# Digital_MEMS_Microphone_Backend.net
KiCad netlist of a schematic drawn in Altium Designer
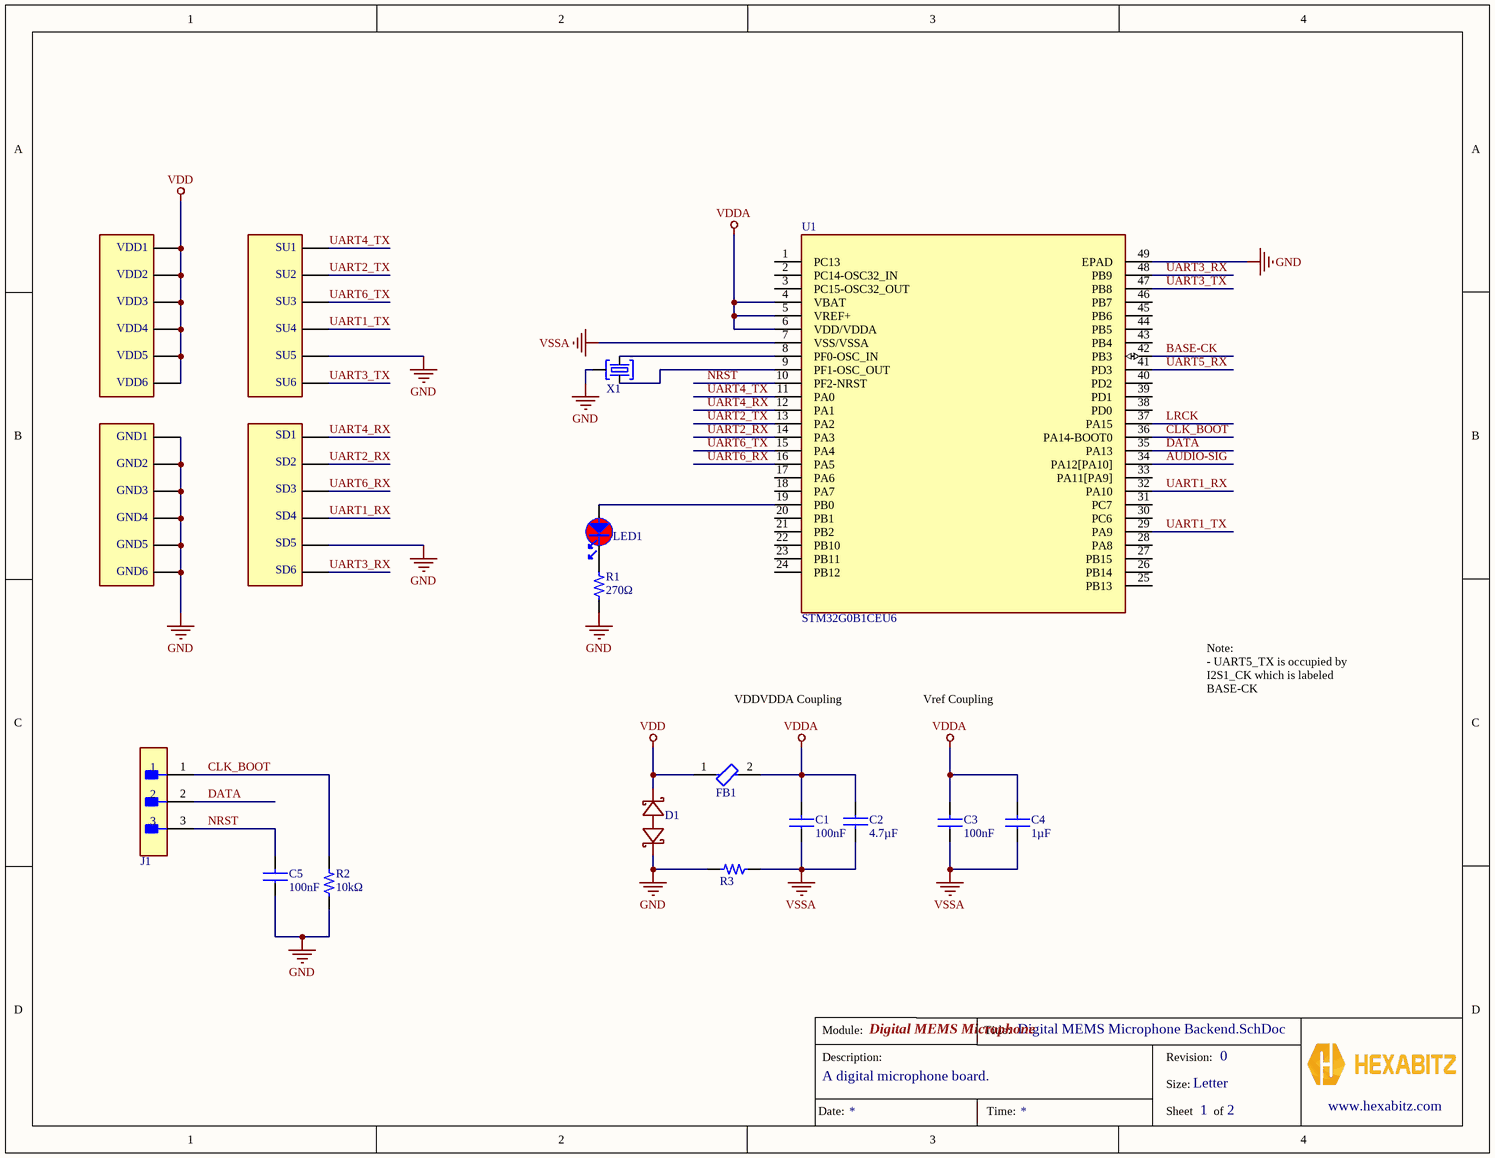
[diagram p0: Digital MEMS Microphone Backend.SchDoc]

(export (version "E")
  (design (tool "Eeschema 10.0.6"))
  (components
    (comp (ref "C1")
      (value "100nF")
      (footprint "C0603")
      (fields
        (field (name "MANUFACTURER") "Samsung Electro-Mechanics")
        (field (name "MANUFACTURER PART NUMBER") "CL10B104KA8NNNC")
        (field (name "TOLERANCE") "10%")
      )
      (libsource (lib "Hexabitz Altium Library") (part "generic Capacitor"))
    )
    (comp (ref "C2")
      (value "4.7µF")
      (footprint "C0805")
      (fields
        (field (name "MANUFACTURER") "Samsung Electro-Mechanics")
        (field (name "MANUFACTURER PART NUMBER") "CL21X475KAQNNNE")
        (field (name "TOLERANCE") "10%")
      )
      (libsource (lib "Hexabitz Altium Library") (part "generic Capacitor"))
    )
    (comp (ref "C3")
      (value "100nF")
      (footprint "C0603")
      (fields
        (field (name "MANUFACTURER") "Samsung Electro-Mechanics")
        (field (name "MANUFACTURER PART NUMBER") "CL10B104KA8NNNC")
        (field (name "TOLERANCE") "10%")
      )
      (libsource (lib "Hexabitz Altium Library") (part "generic Capacitor"))
    )
    (comp (ref "C4")
      (value "1µF")
      (footprint "C0805")
      (description "Ceramic Capacitor, Ceramic, 16V, 10% +Tol, 10% -Tol, X7R, 15% TC, 1uF, Surface Mount, 0805")
      (fields
        (field (name "MANUFACTURER") "Yageo Group")
        (field (name "MANUFACTURER PART NUMBER") "CC0805KKX7R7BB105")
      )
      (libsource (lib "Hexabitz Altium Library") (part "generic Capacitor"))
    )
    (comp (ref "C5")
      (value "100nF")
      (footprint "C0603")
      (fields
        (field (name "MANUFACTURER") "Samsung Electro-Mechanics")
        (field (name "MANUFACTURER PART NUMBER") "CL10B104KA8NNNC")
        (field (name "TOLERANCE") "10%")
      )
      (libsource (lib "Hexabitz Altium Library") (part "generic Capacitor"))
    )
    (comp (ref "D1")
      (value "CDSOD323-T03SC")
      (footprint "SOD2513X114N")
      (description "A 3V, 350W, bi-directional, standard capacitance, SOD323 pkg TVS Diode ¦ Bourns CDSOD323-T03SC")
      (fields (field (name "MANUFACTURER") "Bourns"))
      (libsource (lib "Hexabitz Altium Library") (part "CDSOD323-T03SC"))
    )
    (comp (ref "FB1")
      (value "MMZ1608Y300B")
      (footprint "FP-MMZ1608-0_8-MFG")
      (description "Ferrite Beads 0603 30ohms 1500mA Signal Line AEC-Q200")
      (fields
        (field (name "MANUFACTURER") "TDK")
        (field (name "MANUFACTURER PART NUMBER") "MMZ1608Y300BTD25")
      )
      (libsource (lib "Hexabitz Altium Library") (part "MMZ1608Y300B"))
    )
    (comp (ref "GND1")
      (value "HEXABIT_UART_PORT")
      (footprint "HEXABIT_POWER_PORT_D")
      (libsource (lib "hexabitz_connectors.Library") (part "HEXABIT_POWER_PORT_D"))
    )
    (comp (ref "GND2")
      (value "HEXABIT_UART_PORT")
      (footprint "HEXABIT_POWER_PORT_D")
      (libsource (lib "hexabitz_connectors.Library") (part "HEXABIT_POWER_PORT_D"))
    )
    (comp (ref "GND3")
      (value "HEXABIT_UART_PORT")
      (footprint "HEXABIT_POWER_PORT_D")
      (libsource (lib "hexabitz_connectors.Library") (part "HEXABIT_POWER_PORT_D"))
    )
    (comp (ref "GND4")
      (value "HEXABIT_UART_PORT")
      (footprint "HEXABIT_POWER_PORT_D")
      (libsource (lib "hexabitz_connectors.Library") (part "HEXABIT_POWER_PORT_D"))
    )
    (comp (ref "GND5")
      (value "HEXABIT_UART_PORT")
      (footprint "HEXABIT_POWER_PORT_D")
      (libsource (lib "hexabitz_connectors.Library") (part "HEXABIT_POWER_PORT_D"))
    )
    (comp (ref "GND6")
      (value "HEXABIT_UART_PORT")
      (footprint "HEXABIT_POWER_PORT_D")
      (libsource (lib "hexabitz_connectors.Library") (part "HEXABIT_POWER_PORT_D"))
    )
    (comp (ref "J1")
      (value "TSW-103-14-G-S")
      (footprint "FP-TSW-103-14-G-S-MFG")
      (description "CONN HEADER VERT 3POS 2.54MM")
      (libsource (lib "Altium Content Vault") (part "cd3439d6ef35ae5d9b27ec4fdd3e828"))
    )
    (comp (ref "LED1")
      (value "VLMS1300-GS08")
      (footprint "FP-6_541-5092_01-4-MFG")
      (description "LED Uni-Color Super Red 639nm 2-Pin Chip 0603(1608Metric) T/R")
      (fields (field (name "MANUFACTURER") "Vishay Semiconductors"))
      (libsource (lib "Hexabitz Altium Library") (part "VLMS1300-GS08"))
    )
    (comp (ref "R1")
      (value "270Ω")
      (footprint "R0603")
      (description "Res Thick Film 0603 270 Ohm 5% 0.1W(1/10W) ±200ppm/C Pad SMD Automotive T/R")
      (fields
        (field (name "MANUFACTURER") "Panasonic")
        (field (name "MANUFACTURER PART NUMBER") "ERJ-3GEYJ271V")
      )
      (libsource (lib "") (part "generic Resistor_1"))
    )
    (comp (ref "R2")
      (value "10kΩ")
      (footprint "R0603")
      (description "100mW Thick Film Resistors ±100ppm/℃ ±1% 10kΩ 0603 Chip Resistor - Surface Mount ROHS")
      (fields
        (field (name "MANUFACTURER") "Yageo Group")
        (field (name "MANUFACTURER PART NUMBER") "RC0603FR-0710KL")
      )
      (libsource (lib "Hexabitz Altium Library") (part "generic Resistor"))
    )
    (comp (ref "R3")
      (value "Manufacturer Part Number")
      (footprint "R0603")
      (libsource (lib "") (part "generic Resistor_2"))
    )
    (comp (ref "SD1")
      (value "HEXABIT_UART_PORT")
      (footprint "HEXABIT_UART_PORT_D")
      (libsource (lib "hexabitz_connectors.Library") (part "HEXABIT_UART_PORT_D"))
    )
    (comp (ref "SD2")
      (value "HEXABIT_UART_PORT")
      (footprint "HEXABIT_UART_PORT_D")
      (libsource (lib "hexabitz_connectors.Library") (part "HEXABIT_UART_PORT_D"))
    )
    (comp (ref "SD3")
      (value "HEXABIT_UART_PORT")
      (footprint "HEXABIT_UART_PORT_D")
      (libsource (lib "hexabitz_connectors.Library") (part "HEXABIT_UART_PORT_D"))
    )
    (comp (ref "SD4")
      (value "HEXABIT_UART_PORT")
      (footprint "HEXABIT_UART_PORT_D")
      (libsource (lib "hexabitz_connectors.Library") (part "HEXABIT_UART_PORT_D"))
    )
    (comp (ref "SD5")
      (value "HEXABIT_UART_PORT")
      (footprint "HEXABIT_UART_PORT_D")
      (libsource (lib "hexabitz_connectors.Library") (part "HEXABIT_UART_PORT_D"))
    )
    (comp (ref "SD6")
      (value "HEXABIT_UART_PORT")
      (footprint "HEXABIT_UART_PORT_D")
      (libsource (lib "hexabitz_connectors.Library") (part "HEXABIT_UART_PORT_D"))
    )
    (comp (ref "SU1")
      (value "HEXABIT_UART_PORT")
      (footprint "HEXABIT_UART_PORT_U")
      (libsource (lib "hexabitz_connectors.Library") (part "HEXABIT_UART_PORT_U"))
    )
    (comp (ref "SU2")
      (value "HEXABIT_UART_PORT")
      (footprint "HEXABIT_UART_PORT_U")
      (libsource (lib "hexabitz_connectors.Library") (part "HEXABIT_UART_PORT_U"))
    )
    (comp (ref "SU3")
      (value "HEXABIT_UART_PORT")
      (footprint "HEXABIT_UART_PORT_U")
      (libsource (lib "hexabitz_connectors.Library") (part "HEXABIT_UART_PORT_U"))
    )
    (comp (ref "SU4")
      (value "HEXABIT_UART_PORT")
      (footprint "HEXABIT_UART_PORT_U")
      (libsource (lib "hexabitz_connectors.Library") (part "HEXABIT_UART_PORT_U"))
    )
    (comp (ref "SU5")
      (value "HEXABIT_UART_PORT")
      (footprint "HEXABIT_UART_PORT_U")
      (libsource (lib "hexabitz_connectors.Library") (part "HEXABIT_UART_PORT_U"))
    )
    (comp (ref "SU6")
      (value "HEXABIT_UART_PORT")
      (footprint "HEXABIT_UART_PORT_U")
      (libsource (lib "hexabitz_connectors.Library") (part "HEXABIT_UART_PORT_U"))
    )
    (comp (ref "U1")
      (value "STM32G0B1CEU6")
      (footprint "QFN50P700X700X65-49N-D")
      (description "MCU 32-bit ARM Cortex M0+ RISC 512KB Flash 1.8V/2.5V/3.3V 48-Pin UFQFPN EP Tray")
      (fields
        (field (name "MANUFACTURER") "STMicroelectronics")
        (field (name "MANUFACTURER PART NUMBER") "STM32G0B1CEU6")
      )
      (libsource (lib "Hexabitz Altium Library") (part "STM32G0B1CEU6"))
    )
    (comp (ref "VDD1")
      (value "HEXABIT_UART_PORT")
      (footprint "HEXABIT_POWER_PORT_U")
      (libsource (lib "hexabitz_connectors.Library") (part "HEXABIT_POWER_PORT_U"))
    )
    (comp (ref "VDD2")
      (value "HEXABIT_UART_PORT")
      (footprint "HEXABIT_POWER_PORT_U")
      (libsource (lib "hexabitz_connectors.Library") (part "HEXABIT_POWER_PORT_U"))
    )
    (comp (ref "VDD3")
      (value "HEXABIT_UART_PORT")
      (footprint "HEXABIT_POWER_PORT_U")
      (libsource (lib "hexabitz_connectors.Library") (part "HEXABIT_POWER_PORT_U"))
    )
    (comp (ref "VDD4")
      (value "HEXABIT_UART_PORT")
      (footprint "HEXABIT_POWER_PORT_U")
      (libsource (lib "hexabitz_connectors.Library") (part "HEXABIT_POWER_PORT_U"))
    )
    (comp (ref "VDD5")
      (value "HEXABIT_UART_PORT")
      (footprint "HEXABIT_POWER_PORT_U")
      (libsource (lib "hexabitz_connectors.Library") (part "HEXABIT_POWER_PORT_U"))
    )
    (comp (ref "VDD6")
      (value "HEXABIT_UART_PORT")
      (footprint "HEXABIT_POWER_PORT_U")
      (libsource (lib "hexabitz_connectors.Library") (part "HEXABIT_POWER_PORT_U"))
    )
    (comp (ref "X1")
      (value "CSTCE8M00G52Z-R0")
      (footprint "XTALL_CSTCE8M00G52")
      (description "Ceramic Resonator 8MHz ±0.5% (Tol) ±0.2% (Stability) 10pF 40Ohm 3-Pin CSMD T/R")
      (fields (field (name "MANUFACTURER") "Murata") (field (name "TOLERANCE") "0.5%"))
      (libsource (lib "Hexabitz Altium Library") (part "CSTCE8M00G52Z-R0"))
    )
  )
  (nets
    (net (code "1") (name "/AUDIO-SIG") (class "Default")
      (node (ref "U1") (pin "34") (pinfunction "PA12[PA10]_34") (pintype "passive"))
    )
    (net (code "2") (name "/BASE-CK") (class "Default")
      (node (ref "U1") (pin "42") (pinfunction "PB3_42") (pintype "bidirectional"))
    )
    (net (code "3") (name "/CLK_BOOT") (class "Default")
      (node (ref "J1") (pin "1") (pinfunction "1_1") (pintype "passive"))
      (node (ref "R2") (pin "1") (pinfunction "1_1") (pintype "passive"))
      (node (ref "U1") (pin "36") (pinfunction "PA14-BOOT0_36") (pintype "passive"))
    )
    (net (code "4") (name "/DATA") (class "Default")
      (node (ref "J1") (pin "2") (pinfunction "2_2") (pintype "passive"))
      (node (ref "U1") (pin "35") (pinfunction "PA13_35") (pintype "passive"))
    )
    (net (code "5") (name "/LRCK") (class "Default")
      (node (ref "U1") (pin "37") (pinfunction "PA15_37") (pintype "passive"))
    )
    (net (code "6") (name "/NRST") (class "Default")
      (node (ref "C5") (pin "2") (pinfunction "2_2") (pintype "passive"))
      (node (ref "J1") (pin "3") (pinfunction "3_3") (pintype "passive"))
      (node (ref "U1") (pin "10") (pinfunction "PF2-NRST_10") (pintype "passive"))
    )
    (net (code "7") (name "/UART1_RX") (class "Default")
      (node (ref "SD4") (pin "UART_D") (pinfunction "UART_D_UART_D") (pintype "passive"))
      (node (ref "U1") (pin "32") (pinfunction "PA10_32") (pintype "passive"))
    )
    (net (code "8") (name "/UART1_TX") (class "Default")
      (node (ref "SU4") (pin "UART_U") (pinfunction "UART_U_UART_U") (pintype "passive"))
      (node (ref "U1") (pin "29") (pinfunction "PA9_29") (pintype "passive"))
    )
    (net (code "9") (name "/UART2_RX") (class "Default")
      (node (ref "SD2") (pin "UART_D") (pinfunction "UART_D_UART_D") (pintype "passive"))
      (node (ref "U1") (pin "14") (pinfunction "PA3_14") (pintype "passive"))
    )
    (net (code "10") (name "/UART2_TX") (class "Default")
      (node (ref "SU2") (pin "UART_U") (pinfunction "UART_U_UART_U") (pintype "passive"))
      (node (ref "U1") (pin "13") (pinfunction "PA2_13") (pintype "passive"))
    )
    (net (code "11") (name "/UART3_RX") (class "Default")
      (node (ref "SD6") (pin "UART_D") (pinfunction "UART_D_UART_D") (pintype "passive"))
      (node (ref "U1") (pin "48") (pinfunction "PB9_48") (pintype "passive"))
    )
    (net (code "12") (name "/UART3_TX") (class "Default")
      (node (ref "SU6") (pin "UART_U") (pinfunction "UART_U_UART_U") (pintype "passive"))
      (node (ref "U1") (pin "47") (pinfunction "PB8_47") (pintype "passive"))
    )
    (net (code "13") (name "/UART4_RX") (class "Default")
      (node (ref "SD1") (pin "UART_D") (pinfunction "UART_D_UART_D") (pintype "passive"))
      (node (ref "U1") (pin "12") (pinfunction "PA1_12") (pintype "passive"))
    )
    (net (code "14") (name "/UART4_TX") (class "Default")
      (node (ref "SU1") (pin "UART_U") (pinfunction "UART_U_UART_U") (pintype "passive"))
      (node (ref "U1") (pin "11") (pinfunction "PA0_11") (pintype "passive"))
    )
    (net (code "15") (name "/UART5_RX") (class "Default")
      (node (ref "U1") (pin "41") (pinfunction "PD3_41") (pintype "passive"))
    )
    (net (code "16") (name "/UART6_RX") (class "Default")
      (node (ref "SD3") (pin "UART_D") (pinfunction "UART_D_UART_D") (pintype "passive"))
      (node (ref "U1") (pin "16") (pinfunction "PA5_16") (pintype "passive"))
    )
    (net (code "17") (name "/UART6_TX") (class "Default")
      (node (ref "SU3") (pin "UART_U") (pinfunction "UART_U_UART_U") (pintype "passive"))
      (node (ref "U1") (pin "15") (pinfunction "PA4_15") (pintype "passive"))
    )
    (net (code "18") (name "GND") (class "Default")
      (node (ref "C5") (pin "1") (pinfunction "1_1") (pintype "passive"))
      (node (ref "D1") (pin "1") (pinfunction "A_1") (pintype "passive"))
      (node (ref "GND1") (pin "Pwr_D") (pinfunction "Pwr_D_Pwr_D") (pintype "passive"))
      (node (ref "GND2") (pin "Pwr_D") (pinfunction "Pwr_D_Pwr_D") (pintype "passive"))
      (node (ref "GND3") (pin "Pwr_D") (pinfunction "Pwr_D_Pwr_D") (pintype "passive"))
      (node (ref "GND4") (pin "Pwr_D") (pinfunction "Pwr_D_Pwr_D") (pintype "passive"))
      (node (ref "GND5") (pin "Pwr_D") (pinfunction "Pwr_D_Pwr_D") (pintype "passive"))
      (node (ref "GND6") (pin "Pwr_D") (pinfunction "Pwr_D_Pwr_D") (pintype "passive"))
      (node (ref "R1") (pin "1") (pinfunction "1_1") (pintype "passive"))
      (node (ref "R2") (pin "2") (pinfunction "2_2") (pintype "passive"))
      (node (ref "R3") (pin "1") (pinfunction "1_1") (pintype "passive"))
      (node (ref "SD5") (pin "UART_D") (pinfunction "UART_D_UART_D") (pintype "passive"))
      (node (ref "SU5") (pin "UART_U") (pinfunction "UART_U_UART_U") (pintype "passive"))
      (node (ref "U1") (pin "49") (pinfunction "EPAD_49") (pintype "passive"))
      (node (ref "X1") (pin "P$2") (pinfunction "2_P$2") (pintype "passive"))
    )
    (net (code "19") (name "Net-(LED1-Pad1)") (class "Default")
      (node (ref "LED1") (pin "1") (pintype "passive"))
      (node (ref "R1") (pin "2") (pinfunction "2_2") (pintype "passive"))
    )
    (net (code "20") (name "Net-(U1-PB0)") (class "Default")
      (node (ref "LED1") (pin "2") (pintype "passive"))
      (node (ref "U1") (pin "19") (pinfunction "PB0_19") (pintype "passive"))
    )
    (net (code "21") (name "Net-(U1-PF0-OSC_IN)") (class "Default")
      (node (ref "U1") (pin "8") (pinfunction "PF0-OSC_IN_8") (pintype "passive"))
      (node (ref "X1") (pin "P$3") (pinfunction "3_P$3") (pintype "passive"))
    )
    (net (code "22") (name "Net-(U1-PF1-OSC_OUT)") (class "Default")
      (node (ref "U1") (pin "9") (pinfunction "PF1-OSC_OUT_9") (pintype "passive"))
      (node (ref "X1") (pin "P$1") (pinfunction "1_P$1") (pintype "passive"))
    )
    (net (code "23") (name "VDD") (class "Default")
      (node (ref "D1") (pin "2") (pinfunction "C_2") (pintype "passive"))
      (node (ref "FB1") (pin "1") (pinfunction "1_1") (pintype "passive"))
      (node (ref "VDD1") (pin "Pwr_U") (pinfunction "Pwr_U_Pwr_U") (pintype "passive"))
      (node (ref "VDD2") (pin "Pwr_U") (pinfunction "Pwr_U_Pwr_U") (pintype "passive"))
      (node (ref "VDD3") (pin "Pwr_U") (pinfunction "Pwr_U_Pwr_U") (pintype "passive"))
      (node (ref "VDD4") (pin "Pwr_U") (pinfunction "Pwr_U_Pwr_U") (pintype "passive"))
      (node (ref "VDD5") (pin "Pwr_U") (pinfunction "Pwr_U_Pwr_U") (pintype "passive"))
      (node (ref "VDD6") (pin "Pwr_U") (pinfunction "Pwr_U_Pwr_U") (pintype "passive"))
    )
    (net (code "24") (name "VDDA") (class "Default")
      (node (ref "C1") (pin "2") (pinfunction "2_2") (pintype "passive"))
      (node (ref "C2") (pin "1") (pinfunction "1_1") (pintype "passive"))
      (node (ref "C3") (pin "2") (pinfunction "2_2") (pintype "passive"))
      (node (ref "C4") (pin "2") (pinfunction "2_2") (pintype "passive"))
      (node (ref "FB1") (pin "2") (pinfunction "2_2") (pintype "passive"))
      (node (ref "U1") (pin "4") (pinfunction "VBAT_4") (pintype "passive"))
      (node (ref "U1") (pin "5") (pinfunction "VREF+_5") (pintype "passive"))
      (node (ref "U1") (pin "6") (pinfunction "VDD/VDDA_6") (pintype "passive"))
    )
    (net (code "25") (name "VSSA") (class "Default")
      (node (ref "C1") (pin "1") (pinfunction "1_1") (pintype "passive"))
      (node (ref "C2") (pin "2") (pinfunction "2_2") (pintype "passive"))
      (node (ref "C3") (pin "1") (pinfunction "1_1") (pintype "passive"))
      (node (ref "C4") (pin "1") (pinfunction "1_1") (pintype "passive"))
      (node (ref "R3") (pin "2") (pinfunction "2_2") (pintype "passive"))
      (node (ref "U1") (pin "7") (pinfunction "VSS/VSSA_7") (pintype "passive"))
    )
    (net (code "26") (name "unconnected-(U1-PA6-Pad17)") (class "Default")
      (node (ref "U1") (pin "17") (pinfunction "PA6_17") (pintype "passive"))
    )
    (net (code "27") (name "unconnected-(U1-PA7-Pad18)") (class "Default")
      (node (ref "U1") (pin "18") (pinfunction "PA7_18") (pintype "passive"))
    )
    (net (code "28") (name "unconnected-(U1-PA8-Pad28)") (class "Default")
      (node (ref "U1") (pin "28") (pinfunction "PA8_28") (pintype "passive"))
    )
    (net (code "29") (name "unconnected-(U1-PA11[PA9]-Pad33)") (class "Default")
      (node (ref "U1") (pin "33") (pinfunction "PA11[PA9]_33") (pintype "passive"))
    )
    (net (code "30") (name "unconnected-(U1-PB1-Pad20)") (class "Default")
      (node (ref "U1") (pin "20") (pinfunction "PB1_20") (pintype "passive"))
    )
    (net (code "31") (name "unconnected-(U1-PB2-Pad21)") (class "Default")
      (node (ref "U1") (pin "21") (pinfunction "PB2_21") (pintype "passive"))
    )
    (net (code "32") (name "unconnected-(U1-PB4-Pad43)") (class "Default")
      (node (ref "U1") (pin "43") (pinfunction "PB4_43") (pintype "passive"))
    )
    (net (code "33") (name "unconnected-(U1-PB5-Pad44)") (class "Default")
      (node (ref "U1") (pin "44") (pinfunction "PB5_44") (pintype "passive"))
    )
    (net (code "34") (name "unconnected-(U1-PB6-Pad45)") (class "Default")
      (node (ref "U1") (pin "45") (pinfunction "PB6_45") (pintype "passive"))
    )
    (net (code "35") (name "unconnected-(U1-PB7-Pad46)") (class "Default")
      (node (ref "U1") (pin "46") (pinfunction "PB7_46") (pintype "passive"))
    )
    (net (code "36") (name "unconnected-(U1-PB10-Pad22)") (class "Default")
      (node (ref "U1") (pin "22") (pinfunction "PB10_22") (pintype "passive"))
    )
    (net (code "37") (name "unconnected-(U1-PB11-Pad23)") (class "Default")
      (node (ref "U1") (pin "23") (pinfunction "PB11_23") (pintype "passive"))
    )
    (net (code "38") (name "unconnected-(U1-PB12-Pad24)") (class "Default")
      (node (ref "U1") (pin "24") (pinfunction "PB12_24") (pintype "passive"))
    )
    (net (code "39") (name "unconnected-(U1-PB13-Pad25)") (class "Default")
      (node (ref "U1") (pin "25") (pinfunction "PB13_25") (pintype "passive"))
    )
    (net (code "40") (name "unconnected-(U1-PB14-Pad26)") (class "Default")
      (node (ref "U1") (pin "26") (pinfunction "PB14_26") (pintype "passive"))
    )
    (net (code "41") (name "unconnected-(U1-PB15-Pad27)") (class "Default")
      (node (ref "U1") (pin "27") (pinfunction "PB15_27") (pintype "passive"))
    )
    (net (code "42") (name "unconnected-(U1-PC6-Pad30)") (class "Default")
      (node (ref "U1") (pin "30") (pinfunction "PC6_30") (pintype "passive"))
    )
    (net (code "43") (name "unconnected-(U1-PC7-Pad31)") (class "Default")
      (node (ref "U1") (pin "31") (pinfunction "PC7_31") (pintype "passive"))
    )
    (net (code "44") (name "unconnected-(U1-PC13-Pad1)") (class "Default")
      (node (ref "U1") (pin "1") (pinfunction "PC13_1") (pintype "passive"))
    )
    (net (code "45") (name "unconnected-(U1-PC14-OSC32_IN-Pad2)") (class "Default")
      (node (ref "U1") (pin "2") (pinfunction "PC14-OSC32_IN_2") (pintype "passive"))
    )
    (net (code "46") (name "unconnected-(U1-PC15-OSC32_OUT-Pad3)") (class "Default")
      (node (ref "U1") (pin "3") (pinfunction "PC15-OSC32_OUT_3") (pintype "passive"))
    )
    (net (code "47") (name "unconnected-(U1-PD0-Pad38)") (class "Default")
      (node (ref "U1") (pin "38") (pinfunction "PD0_38") (pintype "passive"))
    )
    (net (code "48") (name "unconnected-(U1-PD1-Pad39)") (class "Default")
      (node (ref "U1") (pin "39") (pinfunction "PD1_39") (pintype "passive"))
    )
    (net (code "49") (name "unconnected-(U1-PD2-Pad40)") (class "Default")
      (node (ref "U1") (pin "40") (pinfunction "PD2_40") (pintype "passive"))
    )
  )
)
